# Configuration.net
KiCad netlist of a schematic drawn in Altium Designer
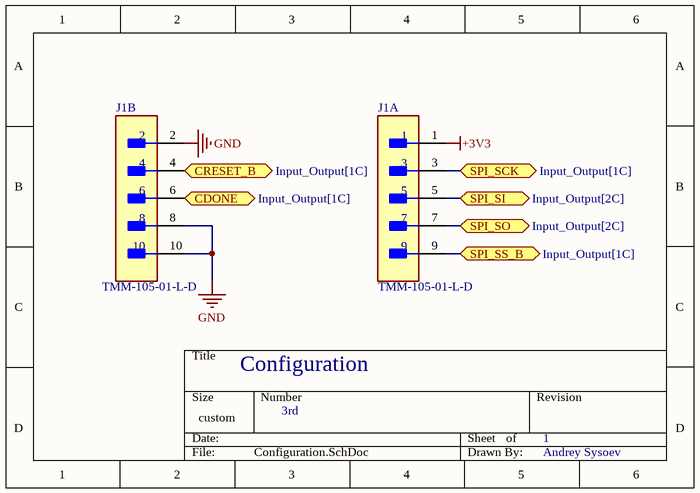
[diagram p0: Configuration.SchDoc]

(export (version "E")
  (design (tool "Eeschema 10.0.6"))
  (components
    (comp (ref "J1")
      (value "TMM-105-01-L-D")
      (footprint "FP-TMM-105-01-L-D-MFG")
      (description "TMM ROHS3Compliant COMMERCIAL 2012 Connector Header -55C~125C 3.2A per Contact 500V 3.94mm")
      (libsource (lib "Andrey Sysoev") (part "837bce96d3219baaf9355552466dfe7"))
    )
  )
  (nets
    (net (code "1") (name "+3V3") (class "Default")
      (node (ref "J1") (pin "1") (pinfunction "1_1") (pintype "passive"))
    )
    (net (code "2") (name "/CDONE") (class "Default")
      (node (ref "J1") (pin "6") (pinfunction "6_6") (pintype "passive"))
    )
    (net (code "3") (name "/CRESET_B") (class "Default")
      (node (ref "J1") (pin "4") (pinfunction "4_4") (pintype "passive"))
    )
    (net (code "4") (name "/SPI_SCK") (class "Default")
      (node (ref "J1") (pin "3") (pinfunction "3_3") (pintype "passive"))
    )
    (net (code "5") (name "/SPI_SI") (class "Default")
      (node (ref "J1") (pin "5") (pinfunction "5_5") (pintype "passive"))
    )
    (net (code "6") (name "/SPI_SO") (class "Default")
      (node (ref "J1") (pin "7") (pinfunction "7_7") (pintype "passive"))
    )
    (net (code "7") (name "/SPI_SS_B") (class "Default")
      (node (ref "J1") (pin "9") (pinfunction "9_9") (pintype "passive"))
    )
    (net (code "8") (name "GND") (class "Default")
      (node (ref "J1") (pin "10") (pinfunction "10_10") (pintype "passive"))
      (node (ref "J1") (pin "2") (pinfunction "2_2") (pintype "passive"))
      (node (ref "J1") (pin "8") (pinfunction "8_8") (pintype "passive"))
    )
  )
)
